# irisc.net
KiCad netlist of a schematic drawn in EAGLE
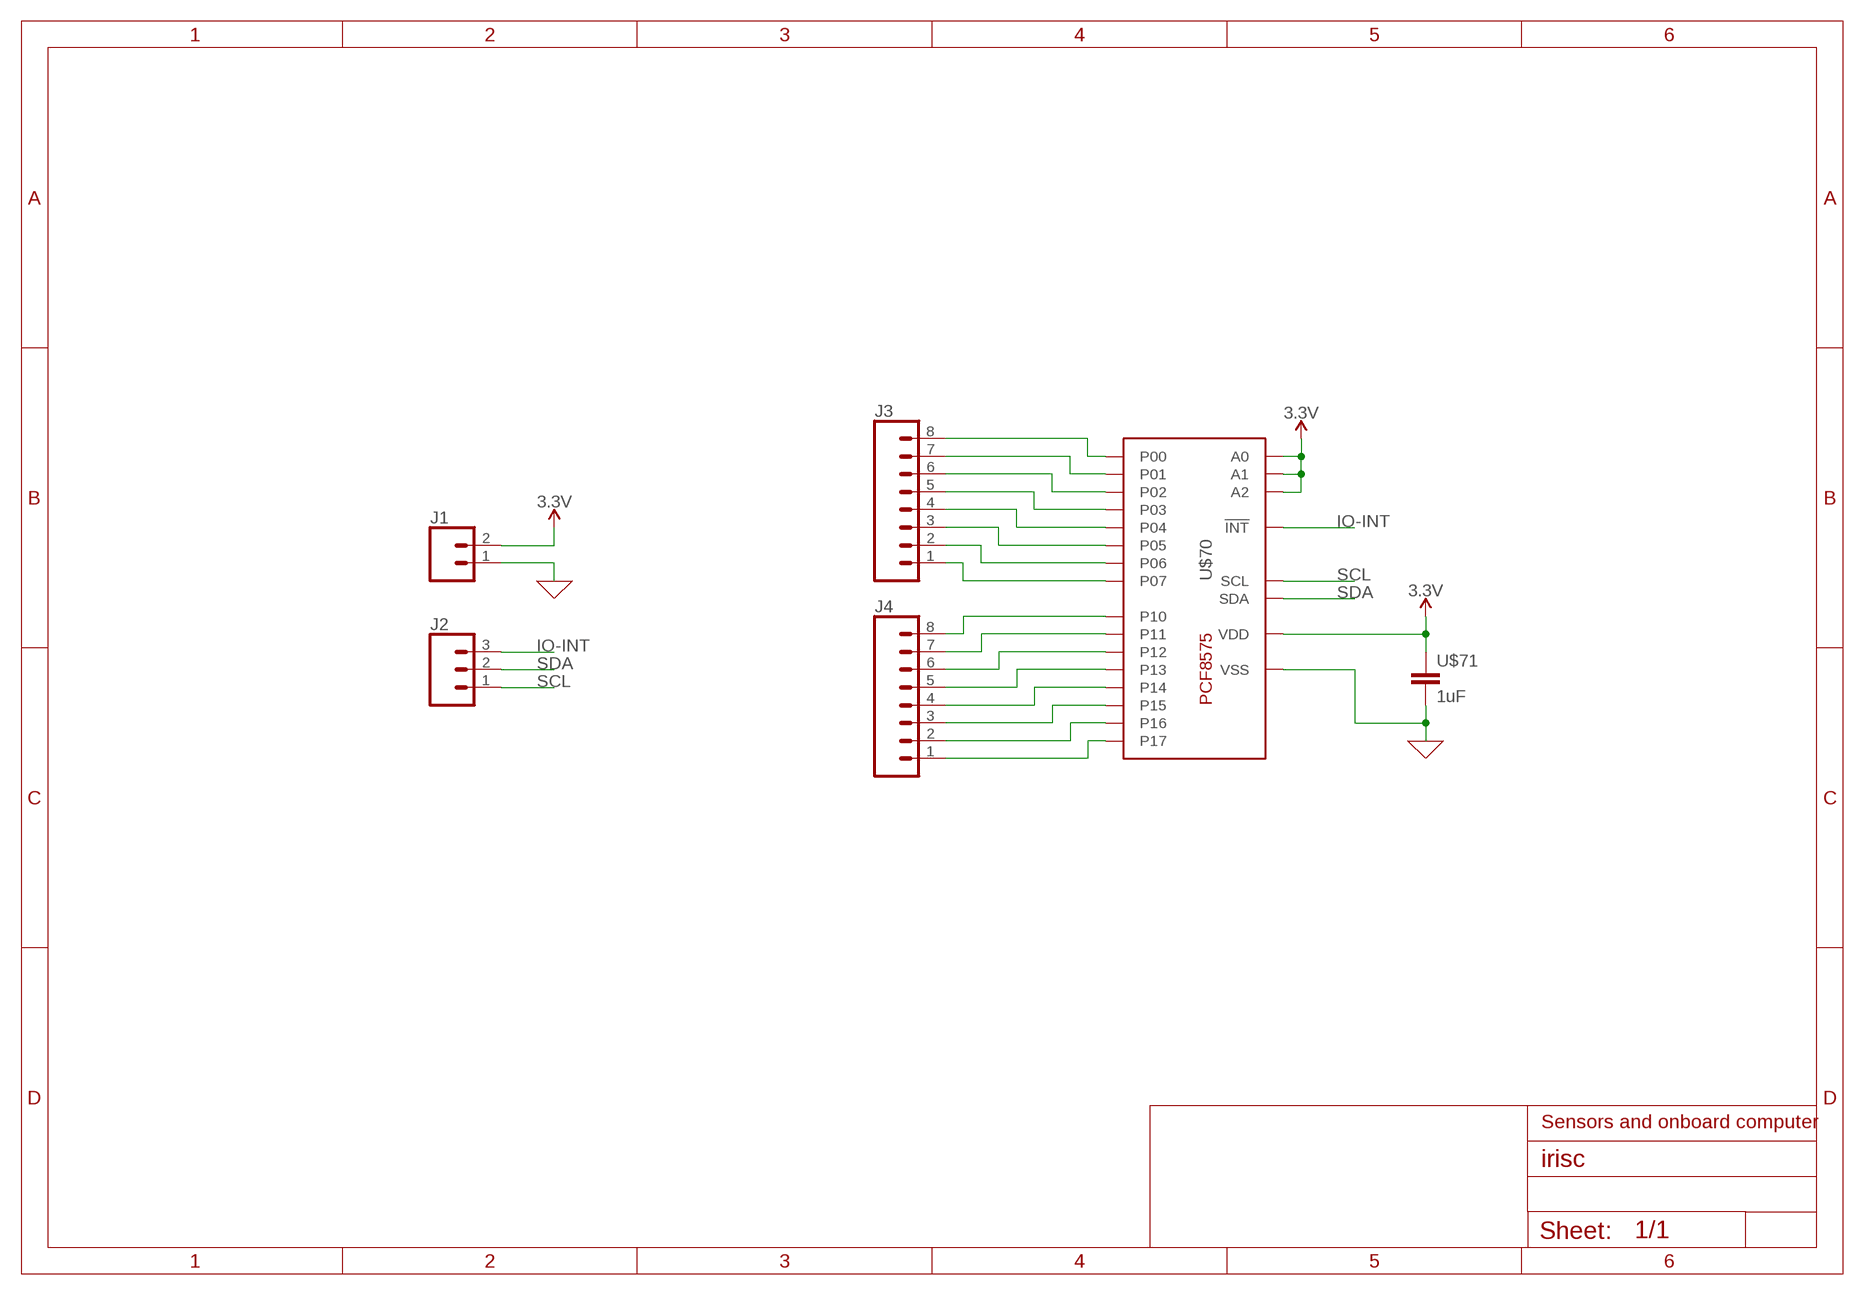
[diagram p0: schematic, sheet 1]

(export (version "E")
  (design (tool "Eeschema 10.0.6"))
  (components
    (comp (ref "J1")
      (value "CONN_02")
      (footprint "eagle-import:1X02")
      (libsource (lib "eagle-import") (part "CONN_02"))
    )
    (comp (ref "J2")
      (value "CONN_03")
      (footprint "eagle-import:1X03")
      (libsource (lib "eagle-import") (part "CONN_03"))
    )
    (comp (ref "J3")
      (value "CONN_08\"")
      (footprint "eagle-import:1X08")
      (libsource (lib "eagle-import") (part "CONN_08{dblquote}"))
    )
    (comp (ref "J4")
      (value "CONN_08\"")
      (footprint "eagle-import:1X08")
      (libsource (lib "eagle-import") (part "CONN_08{dblquote}"))
    )
    (comp (ref "U$70")
      (value "PCF8575CSSOP24N")
      (footprint "eagle-import:SOP65P810X120-24")
      (libsource (lib "eagle-import") (part "PCF8575CSSOP24N"))
    )
    (comp (ref "U$71")
      (value "1uF")
      (footprint "eagle-import:RESC0603_N")
      (libsource (lib "eagle-import") (part "CAPACITOR_0603_N"))
    )
  )
  (nets
    (net (code "1") (name "/IO-INT") (class "Default")
      (node (ref "J2") (pin "3") (pinfunction "3_3") (pintype "passive"))
      (node (ref "U$70") (pin "1") (pinfunction "~{INT}_1") (pintype "open_collector"))
    )
    (net (code "2") (name "/SCL") (class "Default")
      (node (ref "J2") (pin "1") (pinfunction "1_1") (pintype "passive"))
      (node (ref "U$70") (pin "22") (pinfunction "SCL_22") (pintype "input"))
    )
    (net (code "3") (name "/SDA") (class "Default")
      (node (ref "J2") (pin "2") (pinfunction "2_2") (pintype "passive"))
      (node (ref "U$70") (pin "23") (pinfunction "SDA_23") (pintype "bidirectional"))
    )
    (net (code "4") (name "3.3V") (class "Default")
      (node (ref "J1") (pin "2") (pinfunction "2_2") (pintype "passive"))
      (node (ref "U$70") (pin "2") (pinfunction "A1_2") (pintype "input"))
      (node (ref "U$70") (pin "21") (pinfunction "A0_21") (pintype "input"))
      (node (ref "U$70") (pin "24") (pinfunction "VDD_24") (pintype "power_in"))
      (node (ref "U$70") (pin "3") (pinfunction "A2_3") (pintype "input"))
      (node (ref "U$71") (pin "1") (pinfunction "1_1") (pintype "passive"))
    )
    (net (code "5") (name "GND") (class "Default")
      (node (ref "J1") (pin "1") (pinfunction "1_1") (pintype "passive"))
      (node (ref "U$70") (pin "12") (pinfunction "VSS_12") (pintype "power_in"))
      (node (ref "U$71") (pin "2") (pinfunction "2_2") (pintype "passive"))
    )
    (net (code "6") (name "Net-(U$70-P00)") (class "Default")
      (node (ref "J3") (pin "8") (pinfunction "8_8") (pintype "passive"))
      (node (ref "U$70") (pin "4") (pinfunction "P00_4") (pintype "bidirectional"))
    )
    (net (code "7") (name "Net-(U$70-P01)") (class "Default")
      (node (ref "J3") (pin "7") (pinfunction "7_7") (pintype "passive"))
      (node (ref "U$70") (pin "5") (pinfunction "P01_5") (pintype "bidirectional"))
    )
    (net (code "8") (name "Net-(U$70-P02)") (class "Default")
      (node (ref "J3") (pin "6") (pinfunction "6_6") (pintype "passive"))
      (node (ref "U$70") (pin "6") (pinfunction "P02_6") (pintype "bidirectional"))
    )
    (net (code "9") (name "Net-(U$70-P03)") (class "Default")
      (node (ref "J3") (pin "5") (pinfunction "5_5") (pintype "passive"))
      (node (ref "U$70") (pin "7") (pinfunction "P03_7") (pintype "bidirectional"))
    )
    (net (code "10") (name "Net-(U$70-P04)") (class "Default")
      (node (ref "J3") (pin "4") (pinfunction "4_4") (pintype "passive"))
      (node (ref "U$70") (pin "8") (pinfunction "P04_8") (pintype "bidirectional"))
    )
    (net (code "11") (name "Net-(U$70-P05)") (class "Default")
      (node (ref "J3") (pin "3") (pinfunction "3_3") (pintype "passive"))
      (node (ref "U$70") (pin "9") (pinfunction "P05_9") (pintype "bidirectional"))
    )
    (net (code "12") (name "Net-(U$70-P06)") (class "Default")
      (node (ref "J3") (pin "2") (pinfunction "2_2") (pintype "passive"))
      (node (ref "U$70") (pin "10") (pinfunction "P06_10") (pintype "bidirectional"))
    )
    (net (code "13") (name "Net-(U$70-P07)") (class "Default")
      (node (ref "J3") (pin "1") (pinfunction "1_1") (pintype "passive"))
      (node (ref "U$70") (pin "11") (pinfunction "P07_11") (pintype "bidirectional"))
    )
    (net (code "14") (name "Net-(U$70-P10)") (class "Default")
      (node (ref "J4") (pin "8") (pinfunction "8_8") (pintype "passive"))
      (node (ref "U$70") (pin "13") (pinfunction "P10_13") (pintype "bidirectional"))
    )
    (net (code "15") (name "Net-(U$70-P11)") (class "Default")
      (node (ref "J4") (pin "7") (pinfunction "7_7") (pintype "passive"))
      (node (ref "U$70") (pin "14") (pinfunction "P11_14") (pintype "bidirectional"))
    )
    (net (code "16") (name "Net-(U$70-P12)") (class "Default")
      (node (ref "J4") (pin "6") (pinfunction "6_6") (pintype "passive"))
      (node (ref "U$70") (pin "15") (pinfunction "P12_15") (pintype "bidirectional"))
    )
    (net (code "17") (name "Net-(U$70-P13)") (class "Default")
      (node (ref "J4") (pin "5") (pinfunction "5_5") (pintype "passive"))
      (node (ref "U$70") (pin "16") (pinfunction "P13_16") (pintype "bidirectional"))
    )
    (net (code "18") (name "Net-(U$70-P14)") (class "Default")
      (node (ref "J4") (pin "4") (pinfunction "4_4") (pintype "passive"))
      (node (ref "U$70") (pin "17") (pinfunction "P14_17") (pintype "bidirectional"))
    )
    (net (code "19") (name "Net-(U$70-P15)") (class "Default")
      (node (ref "J4") (pin "3") (pinfunction "3_3") (pintype "passive"))
      (node (ref "U$70") (pin "18") (pinfunction "P15_18") (pintype "bidirectional"))
    )
    (net (code "20") (name "Net-(U$70-P16)") (class "Default")
      (node (ref "J4") (pin "2") (pinfunction "2_2") (pintype "passive"))
      (node (ref "U$70") (pin "19") (pinfunction "P16_19") (pintype "bidirectional"))
    )
    (net (code "21") (name "Net-(U$70-P17)") (class "Default")
      (node (ref "J4") (pin "1") (pinfunction "1_1") (pintype "passive"))
      (node (ref "U$70") (pin "20") (pinfunction "P17_20") (pintype "bidirectional"))
    )
  )
)
